# Sheet1.net
KiCad netlist of a schematic drawn in Altium Designer
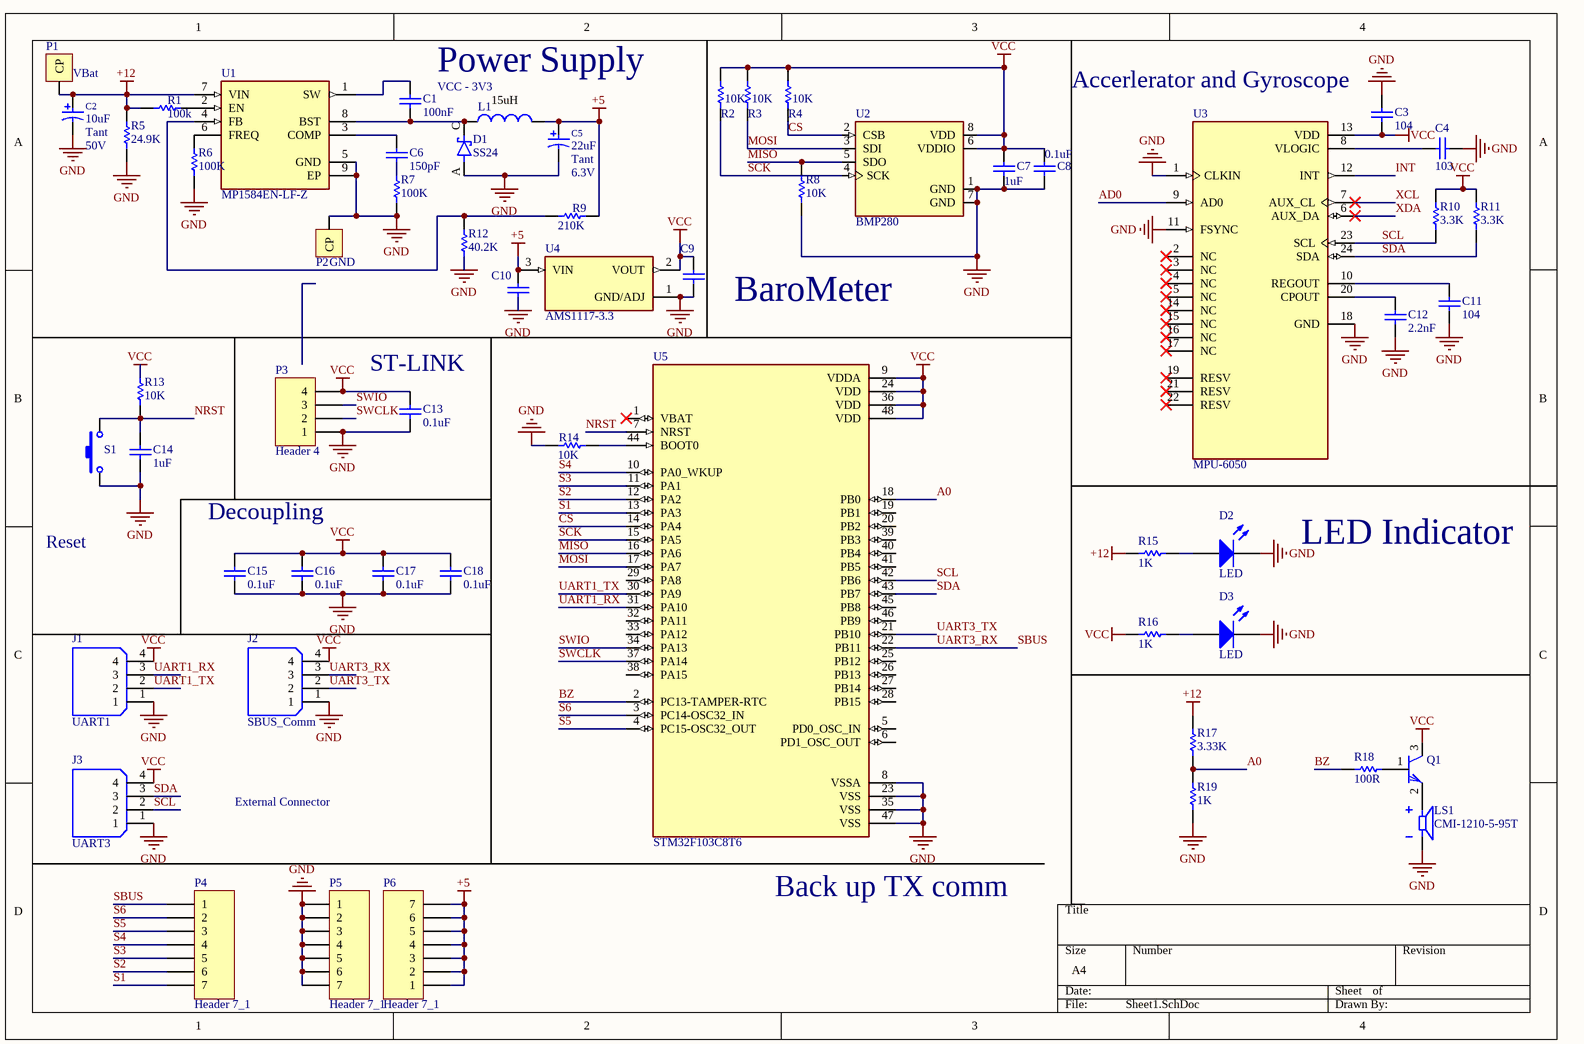
[diagram p0: Sheet1.SchDoc]

(export (version "E")
  (design (tool "Eeschema 10.0.6"))
  (components
    (comp (ref "C1")
      (value "100nF")
      (footprint "C-NP-0805")
      (description "Non-polarized Capacitor")
      (fields (field (name "Comment") "Cap Non-pol") (field (name "PUBLISHER") "Altium Limited"))
      (libsource (lib "Kiet") (part "Cap Non-pol"))
    )
    (comp (ref "C2")
      (value "10uF")
      (footprint "Cap_smd_4_3MM")
      (description "Polarized Capacitor")
      (fields
        (field (name "MANUFACTURER") "FARNELL")
        (field (name "CAPACITOR TYPE") "Tant")
        (field (name "VOLT") "50V")
        (field (name "PUBLISHER") "Hoang Nguyen")
      )
      (libsource (lib "Kiet") (part "Cap_Pol"))
    )
    (comp (ref "C3")
      (value "104")
      (footprint "C-NP-0805")
      (description "Non-polarized Capacitor")
      (fields (field (name "Comment") "Cap Non-pol") (field (name "PUBLISHER") "Altium Limited"))
      (libsource (lib "Kiet") (part "Cap Non-pol"))
    )
    (comp (ref "C4")
      (value "103")
      (footprint "C-NP-0805")
      (description "Non-polarized Capacitor")
      (fields (field (name "Comment") "Cap Non-pol") (field (name "PUBLISHER") "Altium Limited"))
      (libsource (lib "Kiet") (part "Cap Non-pol"))
    )
    (comp (ref "C5")
      (value "22uF")
      (footprint "Cap_smd_4_3MM")
      (description "Polarized Capacitor")
      (fields
        (field (name "MANUFACTURER") "FARNELL")
        (field (name "CAPACITOR TYPE") "Tant")
        (field (name "VOLT") "6.3V")
        (field (name "PUBLISHER") "Hoang Nguyen")
      )
      (libsource (lib "Kiet") (part "Cap_Pol"))
    )
    (comp (ref "C6")
      (value "150pF")
      (footprint "C-NP-0805")
      (description "Non-polarized Capacitor")
      (fields (field (name "Comment") "Cap Non-pol") (field (name "PUBLISHER") "Altium Limited"))
      (libsource (lib "Kiet") (part "Cap Non-pol"))
    )
    (comp (ref "C7")
      (value "1uF")
      (footprint "C-NP-0805")
      (description "Non-polarized Capacitor")
      (fields (field (name "Comment") "Cap Non-pol") (field (name "PUBLISHER") "Altium Limited"))
      (libsource (lib "Kiet") (part "Cap Non-pol"))
    )
    (comp (ref "C8")
      (value "0.1uF")
      (footprint "C-NP-0805")
      (description "Non-polarized Capacitor")
      (fields (field (name "Comment") "Cap Non-pol") (field (name "PUBLISHER") "Altium Limited"))
      (libsource (lib "Kiet") (part "Cap Non-pol"))
    )
    (comp (ref "C9")
      (value "Cap Non-pol")
      (footprint "C-NP-0805")
      (description "Non-polarized Capacitor")
      (fields (field (name "PUBLISHER") "Altium Limited"))
      (libsource (lib "Kiet") (part "Cap Non-pol"))
    )
    (comp (ref "C10")
      (value "Cap Non-pol")
      (footprint "C-NP-0805")
      (description "Non-polarized Capacitor")
      (fields (field (name "PUBLISHER") "Altium Limited"))
      (libsource (lib "Kiet") (part "Cap Non-pol"))
    )
    (comp (ref "C11")
      (value "104")
      (footprint "C-NP-0805")
      (description "Non-polarized Capacitor")
      (fields (field (name "Comment") "Cap Non-pol") (field (name "PUBLISHER") "Altium Limited"))
      (libsource (lib "Kiet") (part "Cap Non-pol"))
    )
    (comp (ref "C12")
      (value "2.2nF")
      (footprint "C-NP-0805")
      (description "Non-polarized Capacitor")
      (fields (field (name "Comment") "Cap Non-pol") (field (name "PUBLISHER") "Altium Limited"))
      (libsource (lib "Kiet") (part "Cap Non-pol"))
    )
    (comp (ref "C13")
      (value "0.1uF")
      (footprint "C-NP-0805")
      (description "Non-polarized Capacitor")
      (fields (field (name "Comment") "Cap Non-pol") (field (name "PUBLISHER") "Altium Limited"))
      (libsource (lib "Kiet") (part "Cap Non-pol"))
    )
    (comp (ref "C14")
      (value "1uF")
      (footprint "C-NP-0805")
      (description "Non-polarized Capacitor")
      (fields (field (name "Comment") "Cap Non-pol") (field (name "PUBLISHER") "Altium Limited"))
      (libsource (lib "Kiet") (part "Cap Non-pol"))
    )
    (comp (ref "C15")
      (value "0.1uF")
      (footprint "C-NP-0805")
      (description "Non-polarized Capacitor")
      (fields (field (name "Comment") "Cap Non-pol") (field (name "PUBLISHER") "Altium Limited"))
      (libsource (lib "Kiet") (part "Cap Non-pol"))
    )
    (comp (ref "C16")
      (value "0.1uF")
      (footprint "C-NP-0805")
      (description "Non-polarized Capacitor")
      (fields (field (name "Comment") "Cap Non-pol") (field (name "PUBLISHER") "Altium Limited"))
      (libsource (lib "Kiet") (part "Cap Non-pol"))
    )
    (comp (ref "C17")
      (value "0.1uF")
      (footprint "C-NP-0805")
      (description "Non-polarized Capacitor")
      (fields (field (name "Comment") "Cap Non-pol") (field (name "PUBLISHER") "Altium Limited"))
      (libsource (lib "Kiet") (part "Cap Non-pol"))
    )
    (comp (ref "C18")
      (value "0.1uF")
      (footprint "C-NP-0805")
      (description "Non-polarized Capacitor")
      (fields (field (name "Comment") "Cap Non-pol") (field (name "PUBLISHER") "Altium Limited"))
      (libsource (lib "Kiet") (part "Cap Non-pol"))
    )
    (comp (ref "D1")
      (value "SS24")
      (footprint "DIOM5336X265N")
      (description "Diode Schottky 40V 2A Surface Mount DO-214AA (SMB)")
      (fields (field (name "MF") "ON Semiconductor"))
      (libsource (lib "SS24") (part "SS24"))
    )
    (comp (ref "D2")
      (value "LED")
      (footprint "LED-0805 GREEN")
      (description "Typical LED")
      (fields (field (name "PUBLISHER") "Altium Limited"))
      (libsource (lib "Kiet") (part "LED"))
    )
    (comp (ref "D3")
      (value "LED")
      (footprint "LED-0805 GREEN")
      (description "Typical LED")
      (fields (field (name "PUBLISHER") "Altium Limited"))
      (libsource (lib "Kiet") (part "LED"))
    )
    (comp (ref "J1")
      (value "UART1")
      (footprint "AMPHENOL_10114830-11104LF")
      (fields
        (field (name "MF") "{'manufacturer': u'Amphenol ICC (FCI)'}")
        (field (name "MP") "10114830-11104LF")
      )
      (libsource (lib "1.25_SMD_4P_connector") (part "10114830-11104LF"))
    )
    (comp (ref "J2")
      (value "SBUS_Comm")
      (footprint "AMPHENOL_10114830-11104LF")
      (fields
        (field (name "MF") "{'manufacturer': u'Amphenol ICC (FCI)'}")
        (field (name "MP") "10114830-11104LF")
      )
      (libsource (lib "1.25_SMD_4P_connector") (part "10114830-11104LF"))
    )
    (comp (ref "J3")
      (value "UART3")
      (footprint "AMPHENOL_10114830-11104LF")
      (fields
        (field (name "MF") "{'manufacturer': u'Amphenol ICC (FCI)'}")
        (field (name "MP") "10114830-11104LF")
      )
      (libsource (lib "1.25_SMD_4P_connector") (part "10114830-11104LF"))
    )
    (comp (ref "L1")
      (value "15uH")
      (footprint "IMPE7-RS1")
      (description "Cuon Cam L")
      (fields (field (name "PUBLISHER") "Altium Limited"))
      (libsource (lib "Kiet") (part "Inductor_1"))
    )
    (comp (ref "LS1")
      (value "CMI-1210-5-95T")
      (footprint "XDCR_CMI-1210-5-95T")
      (description "12 mm, 5 Vdc, 98 dB, Through Hole, Magnetic Audio Indicator Buzzer")
      (fields (field (name "MF") "Same Sky"))
      (libsource (lib "Buzzer") (part "CMI-1210-5-95T"))
    )
    (comp (ref "P1")
      (value "VBat")
      (footprint "CP")
      (description "Connect Pad, 1-Pin")
      (fields (field (name "PUBLISHER") "Altium Limited"))
      (libsource (lib "Kiet") (part "Connect Pad"))
    )
    (comp (ref "P2")
      (value "GND")
      (footprint "CP")
      (description "Connect Pad, 1-Pin")
      (fields (field (name "PUBLISHER") "Altium Limited"))
      (libsource (lib "") (part "Connect Pad_1"))
    )
    (comp (ref "P3")
      (value "Header 4")
      (footprint "Header 4")
      (description "Header, 4-Pin")
      (fields (field (name "PUBLISHER") "Altium Limited"))
      (libsource (lib "Kiet") (part "Header 4"))
    )
    (comp (ref "P4")
      (value "Header 7_1")
      (footprint "HDR1X7")
      (description "Header, 7-Pin")
      (fields (field (name "PUBLISHER") "Altium Limited"))
      (libsource (lib "Kiet") (part "Header 7_1"))
    )
    (comp (ref "P5")
      (value "Header 7_1")
      (footprint "HDR1X7")
      (description "Header, 7-Pin")
      (fields (field (name "PUBLISHER") "Altium Limited"))
      (libsource (lib "Kiet") (part "Header 7_1"))
    )
    (comp (ref "P6")
      (value "Header 7_1")
      (footprint "HDR1X7")
      (description "Header, 7-Pin")
      (fields (field (name "PUBLISHER") "Altium Limited"))
      (libsource (lib "") (part "Header 7_1_1"))
    )
    (comp (ref "Q1")
      (value "C1815")
      (footprint "SOT23 [C1815]")
      (description "Q2SC1815")
      (fields (field (name "PUBLISHER") "Hoang Nguyen"))
      (libsource (lib "Kiet") (part "C1815"))
    )
    (comp (ref "R1")
      (value "100k")
      (footprint "R-0805")
      (description "Resistor")
      (fields (field (name "Comment") "RESISTOR") (field (name "PUBLISHER") "Altium Limited"))
      (libsource (lib "Kiet") (part "RESISTOR"))
    )
    (comp (ref "R2")
      (value "10K")
      (footprint "R-0805")
      (description "Resistor")
      (fields (field (name "Comment") "RESISTOR") (field (name "PUBLISHER") "Altium Limited"))
      (libsource (lib "Kiet") (part "RESISTOR"))
    )
    (comp (ref "R3")
      (value "10K")
      (footprint "R-0805")
      (description "Resistor")
      (fields (field (name "Comment") "RESISTOR") (field (name "PUBLISHER") "Altium Limited"))
      (libsource (lib "Kiet") (part "RESISTOR"))
    )
    (comp (ref "R4")
      (value "10K")
      (footprint "R-0805")
      (description "Resistor")
      (fields (field (name "Comment") "RESISTOR") (field (name "PUBLISHER") "Altium Limited"))
      (libsource (lib "Kiet") (part "RESISTOR"))
    )
    (comp (ref "R5")
      (value "24.9K")
      (footprint "R-0805")
      (description "Resistor")
      (fields (field (name "Comment") "RESISTOR") (field (name "PUBLISHER") "Altium Limited"))
      (libsource (lib "Kiet") (part "RESISTOR"))
    )
    (comp (ref "R6")
      (value "100K")
      (footprint "R-0805")
      (description "Resistor")
      (fields (field (name "Comment") "RESISTOR") (field (name "PUBLISHER") "Altium Limited"))
      (libsource (lib "Kiet") (part "RESISTOR"))
    )
    (comp (ref "R7")
      (value "100K")
      (footprint "R-0805")
      (description "Resistor")
      (fields (field (name "Comment") "RESISTOR") (field (name "PUBLISHER") "Altium Limited"))
      (libsource (lib "Kiet") (part "RESISTOR"))
    )
    (comp (ref "R8")
      (value "10K")
      (footprint "R-0805")
      (description "Resistor")
      (fields (field (name "Comment") "RESISTOR") (field (name "PUBLISHER") "Altium Limited"))
      (libsource (lib "Kiet") (part "RESISTOR"))
    )
    (comp (ref "R9")
      (value "210K")
      (footprint "R-0805")
      (description "Resistor")
      (fields (field (name "Comment") "RESISTOR") (field (name "PUBLISHER") "Altium Limited"))
      (libsource (lib "Kiet") (part "RESISTOR"))
    )
    (comp (ref "R10")
      (value "3.3K")
      (footprint "R-0805")
      (description "Resistor")
      (fields (field (name "Comment") "RESISTOR") (field (name "PUBLISHER") "Altium Limited"))
      (libsource (lib "Kiet") (part "RESISTOR"))
    )
    (comp (ref "R11")
      (value "3.3K")
      (footprint "R-0805")
      (description "Resistor")
      (fields (field (name "Comment") "RESISTOR") (field (name "PUBLISHER") "Altium Limited"))
      (libsource (lib "Kiet") (part "RESISTOR"))
    )
    (comp (ref "R12")
      (value "40.2K")
      (footprint "R-0805")
      (description "Resistor")
      (fields (field (name "Comment") "RESISTOR") (field (name "PUBLISHER") "Altium Limited"))
      (libsource (lib "Kiet") (part "RESISTOR"))
    )
    (comp (ref "R13")
      (value "10K")
      (footprint "R-0805")
      (description "Resistor")
      (fields (field (name "Comment") "RESISTOR") (field (name "PUBLISHER") "Altium Limited"))
      (libsource (lib "Kiet") (part "RESISTOR"))
    )
    (comp (ref "R14")
      (value "10K")
      (footprint "R-0805")
      (description "Resistor")
      (fields (field (name "Comment") "RESISTOR") (field (name "PUBLISHER") "Altium Limited"))
      (libsource (lib "Kiet") (part "RESISTOR"))
    )
    (comp (ref "R15")
      (value "1K")
      (footprint "R-0805")
      (description "Resistor")
      (fields (field (name "Comment") "RESISTOR") (field (name "PUBLISHER") "Altium Limited"))
      (libsource (lib "Kiet") (part "RESISTOR"))
    )
    (comp (ref "R16")
      (value "1K")
      (footprint "R-0805")
      (description "Resistor")
      (fields (field (name "Comment") "RESISTOR") (field (name "PUBLISHER") "Altium Limited"))
      (libsource (lib "Kiet") (part "RESISTOR"))
    )
    (comp (ref "R17")
      (value "3.33K")
      (footprint "R-0805")
      (description "Resistor")
      (fields (field (name "Comment") "RESISTOR") (field (name "PUBLISHER") "Altium Limited"))
      (libsource (lib "Kiet") (part "RESISTOR"))
    )
    (comp (ref "R18")
      (value "100R")
      (footprint "R-0805")
      (description "Resistor")
      (fields (field (name "Comment") "RESISTOR") (field (name "PUBLISHER") "Altium Limited"))
      (libsource (lib "Kiet") (part "RESISTOR"))
    )
    (comp (ref "R19")
      (value "1K")
      (footprint "R-0805")
      (description "Resistor")
      (fields (field (name "Comment") "RESISTOR") (field (name "PUBLISHER") "Altium Limited"))
      (libsource (lib "Kiet") (part "RESISTOR"))
    )
    (comp (ref "S1")
      (value "SW-SMD")
      (footprint "SW-SMD")
      (description "Switch")
      (fields (field (name "PUBLISHER") "Altium Limited"))
      (libsource (lib "Kiet") (part "SW-SMD"))
    )
    (comp (ref "U1")
      (value "MP1584EN-LF-Z")
      (footprint "SOIC127P600X170-9N")
      (fields (field (name "MF") "Monolithic Power Systems") (field (name "MP") "MP1584ENLFZ"))
      (libsource (lib "MP1584EN-LF-Z") (part "MP1584EN-LF-Z"))
    )
    (comp (ref "U2")
      (value "BMP280")
      (footprint "XDCR_BMP280")
      (description "BMP280 Absolute Barometric Pressure Sensor for Battery Powered Devices 2 x 2.5mm")
      (libsource (lib "BMP280") (part "BMP280"))
    )
    (comp (ref "U3")
      (value "MPU-6050")
      (footprint "QFN50P400X400X95-24N")
      (description "MPU-6050 series Accelerometer, Gyroscope, 3 Axis Sensor Evaluation Board")
      (fields (field (name "MF") "TDK InvenSense"))
      (libsource (lib "MPU-6050") (part "MPU-6050"))
    )
    (comp (ref "U4")
      (value "AMS1117-3.3")
      (footprint "SOT229P700X180-4N")
      (description "Sot223/Pkg 1-Amp 3.3-Volt Low Drop Out Voltage Regulatator")
      (fields (field (name "MF") "Advanced Monolithic Systems"))
      (libsource (lib "AMS1117-3.3") (part "AMS1117-3.3"))
    )
    (comp (ref "U5")
      (value "STM32F103C8T6")
      (footprint "QFP50P900X900X160-48N")
      (description "ARM® Cortex®-M3 STM32F1 Microcontroller IC 32-Bit 72MHz 64KB (64K x 8) FLASH 48-LQFP (7x7)")
      (fields (field (name "MF") "STMicroelectronics"))
      (libsource (lib "STM32F103C8T6") (part "STM32F103C8T6"))
    )
  )
  (nets
    (net (code "1") (name "+5") (class "Default")
      (node (ref "C10") (pin "1") (pinfunction "1_1") (pintype "passive"))
      (node (ref "C5") (pin "1") (pinfunction "1_1") (pintype "passive"))
      (node (ref "L1") (pin "2") (pinfunction "2_2") (pintype "passive"))
      (node (ref "P6") (pin "1") (pinfunction "1_1") (pintype "passive"))
      (node (ref "P6") (pin "2") (pinfunction "2_2") (pintype "passive"))
      (node (ref "P6") (pin "3") (pinfunction "3_3") (pintype "passive"))
      (node (ref "P6") (pin "4") (pinfunction "4_4") (pintype "passive"))
      (node (ref "P6") (pin "5") (pinfunction "5_5") (pintype "passive"))
      (node (ref "P6") (pin "6") (pinfunction "6_6") (pintype "passive"))
      (node (ref "P6") (pin "7") (pinfunction "7_7") (pintype "passive"))
      (node (ref "R9") (pin "1") (pinfunction "1_1") (pintype "passive"))
      (node (ref "U4") (pin "3") (pinfunction "VIN_3") (pintype "input"))
    )
    (net (code "2") (name "+12") (class "Default")
      (node (ref "C2") (pin "1") (pinfunction "1_1") (pintype "passive"))
      (node (ref "P1") (pin "1") (pinfunction "CP_1") (pintype "passive"))
      (node (ref "R1") (pin "1") (pinfunction "1_1") (pintype "passive"))
      (node (ref "R15") (pin "2") (pinfunction "2_2") (pintype "passive"))
      (node (ref "R17") (pin "1") (pinfunction "1_1") (pintype "passive"))
      (node (ref "R5") (pin "2") (pinfunction "2_2") (pintype "passive"))
      (node (ref "U1") (pin "7") (pinfunction "VIN_7") (pintype "input"))
    )
    (net (code "3") (name "/A0") (class "Default")
      (node (ref "R17") (pin "2") (pinfunction "2_2") (pintype "passive"))
      (node (ref "R19") (pin "1") (pinfunction "1_1") (pintype "passive"))
      (node (ref "U5") (pin "18") (pinfunction "PB0_18") (pintype "bidirectional"))
    )
    (net (code "4") (name "/AD0") (class "Default")
      (node (ref "U3") (pin "9") (pinfunction "AD0_9") (pintype "input"))
    )
    (net (code "5") (name "/BZ") (class "Default")
      (node (ref "R18") (pin "1") (pinfunction "1_1") (pintype "passive"))
      (node (ref "U5") (pin "2") (pinfunction "PC13-TAMPER-RTC_2") (pintype "bidirectional"))
    )
    (net (code "6") (name "/CS") (class "Default")
      (node (ref "R4") (pin "2") (pinfunction "2_2") (pintype "passive"))
      (node (ref "U2") (pin "2") (pinfunction "CSB_2") (pintype "input"))
      (node (ref "U5") (pin "14") (pinfunction "PA4_14") (pintype "bidirectional"))
    )
    (net (code "7") (name "/INT") (class "Default")
      (node (ref "U3") (pin "12") (pinfunction "INT_12") (pintype "output"))
    )
    (net (code "8") (name "/MISO") (class "Default")
      (node (ref "R8") (pin "1") (pinfunction "1_1") (pintype "passive"))
      (node (ref "U2") (pin "5") (pinfunction "SDO_5") (pintype "bidirectional"))
      (node (ref "U5") (pin "16") (pinfunction "PA6_16") (pintype "bidirectional"))
    )
    (net (code "9") (name "/MOSI") (class "Default")
      (node (ref "R3") (pin "2") (pinfunction "2_2") (pintype "passive"))
      (node (ref "U2") (pin "3") (pinfunction "SDI_3") (pintype "bidirectional"))
      (node (ref "U5") (pin "17") (pinfunction "PA7_17") (pintype "bidirectional"))
    )
    (net (code "10") (name "/NRST") (class "Default")
      (node (ref "C14") (pin "1") (pinfunction "1_1") (pintype "passive"))
      (node (ref "R13") (pin "2") (pinfunction "2_2") (pintype "passive"))
      (node (ref "S1") (pin "2") (pinfunction "2_2") (pintype "passive"))
      (node (ref "U5") (pin "7") (pinfunction "NRST_7") (pintype "input"))
    )
    (net (code "11") (name "/S1") (class "Default")
      (node (ref "P4") (pin "7") (pinfunction "7_7") (pintype "passive"))
      (node (ref "U5") (pin "13") (pinfunction "PA3_13") (pintype "bidirectional"))
    )
    (net (code "12") (name "/S2") (class "Default")
      (node (ref "P4") (pin "6") (pinfunction "6_6") (pintype "passive"))
      (node (ref "U5") (pin "12") (pinfunction "PA2_12") (pintype "bidirectional"))
    )
    (net (code "13") (name "/S3") (class "Default")
      (node (ref "P4") (pin "5") (pinfunction "5_5") (pintype "passive"))
      (node (ref "U5") (pin "11") (pinfunction "PA1_11") (pintype "bidirectional"))
    )
    (net (code "14") (name "/S4") (class "Default")
      (node (ref "P4") (pin "4") (pinfunction "4_4") (pintype "passive"))
      (node (ref "U5") (pin "10") (pinfunction "PA0_WKUP_10") (pintype "bidirectional"))
    )
    (net (code "15") (name "/S5") (class "Default")
      (node (ref "P4") (pin "3") (pinfunction "3_3") (pintype "passive"))
      (node (ref "U5") (pin "4") (pinfunction "PC15-OSC32_OUT_4") (pintype "bidirectional"))
    )
    (net (code "16") (name "/S6") (class "Default")
      (node (ref "P4") (pin "2") (pinfunction "2_2") (pintype "passive"))
      (node (ref "U5") (pin "3") (pinfunction "PC14-OSC32_IN_3") (pintype "bidirectional"))
    )
    (net (code "17") (name "/SBUS") (class "Default")
      (node (ref "J2") (pin "3") (pinfunction "3_3") (pintype "passive"))
      (node (ref "P4") (pin "1") (pinfunction "1_1") (pintype "passive"))
      (node (ref "U5") (pin "22") (pinfunction "PB11_22") (pintype "bidirectional"))
    )
    (net (code "18") (name "/SCK") (class "Default")
      (node (ref "R2") (pin "2") (pinfunction "2_2") (pintype "passive"))
      (node (ref "U2") (pin "4") (pinfunction "SCK_4") (pintype "input"))
      (node (ref "U5") (pin "15") (pinfunction "PA5_15") (pintype "bidirectional"))
    )
    (net (code "19") (name "/SCL") (class "Default")
      (node (ref "J3") (pin "2") (pinfunction "2_2") (pintype "passive"))
      (node (ref "R10") (pin "2") (pinfunction "2_2") (pintype "passive"))
      (node (ref "U3") (pin "23") (pinfunction "SCL_23") (pintype "input"))
      (node (ref "U5") (pin "42") (pinfunction "PB6_42") (pintype "bidirectional"))
    )
    (net (code "20") (name "/SDA") (class "Default")
      (node (ref "J3") (pin "3") (pinfunction "3_3") (pintype "passive"))
      (node (ref "R11") (pin "2") (pinfunction "2_2") (pintype "passive"))
      (node (ref "U3") (pin "24") (pinfunction "SDA_24") (pintype "bidirectional"))
      (node (ref "U5") (pin "43") (pinfunction "PB7_43") (pintype "bidirectional"))
    )
    (net (code "21") (name "/SWCLK") (class "Default")
      (node (ref "P3") (pin "2") (pinfunction "2_2") (pintype "passive"))
      (node (ref "U5") (pin "37") (pinfunction "PA14_37") (pintype "bidirectional"))
    )
    (net (code "22") (name "/SWIO") (class "Default")
      (node (ref "P3") (pin "3") (pinfunction "3_3") (pintype "passive"))
      (node (ref "U5") (pin "34") (pinfunction "PA13_34") (pintype "bidirectional"))
    )
    (net (code "23") (name "/UART1_RX") (class "Default")
      (node (ref "J1") (pin "3") (pinfunction "3_3") (pintype "passive"))
      (node (ref "U5") (pin "31") (pinfunction "PA10_31") (pintype "bidirectional"))
    )
    (net (code "24") (name "/UART1_TX") (class "Default")
      (node (ref "J1") (pin "2") (pinfunction "2_2") (pintype "passive"))
      (node (ref "U5") (pin "30") (pinfunction "PA9_30") (pintype "bidirectional"))
    )
    (net (code "25") (name "/UART3_TX") (class "Default")
      (node (ref "J2") (pin "2") (pinfunction "2_2") (pintype "passive"))
      (node (ref "U5") (pin "21") (pinfunction "PB10_21") (pintype "bidirectional"))
    )
    (net (code "26") (name "/XCL") (class "Default")
      (node (ref "U3") (pin "7") (pinfunction "AUX_CL_7") (pintype "output+no_connect"))
    )
    (net (code "27") (name "/XDA") (class "Default")
      (node (ref "U3") (pin "6") (pinfunction "AUX_DA_6") (pintype "bidirectional+no_connect"))
    )
    (net (code "28") (name "GND") (class "Default")
      (node (ref "C10") (pin "2") (pinfunction "2_2") (pintype "passive"))
      (node (ref "C11") (pin "1") (pinfunction "1_1") (pintype "passive"))
      (node (ref "C12") (pin "1") (pinfunction "1_1") (pintype "passive"))
      (node (ref "C13") (pin "2") (pinfunction "2_2") (pintype "passive"))
      (node (ref "C14") (pin "2") (pinfunction "2_2") (pintype "passive"))
      (node (ref "C15") (pin "2") (pinfunction "2_2") (pintype "passive"))
      (node (ref "C16") (pin "2") (pinfunction "2_2") (pintype "passive"))
      (node (ref "C17") (pin "2") (pinfunction "2_2") (pintype "passive"))
      (node (ref "C18") (pin "2") (pinfunction "2_2") (pintype "passive"))
      (node (ref "C2") (pin "2") (pinfunction "2_2") (pintype "passive"))
      (node (ref "C3") (pin "2") (pinfunction "2_2") (pintype "passive"))
      (node (ref "C4") (pin "2") (pinfunction "2_2") (pintype "passive"))
      (node (ref "C5") (pin "2") (pinfunction "2_2") (pintype "passive"))
      (node (ref "C7") (pin "2") (pinfunction "2_2") (pintype "passive"))
      (node (ref "C8") (pin "2") (pinfunction "2_2") (pintype "passive"))
      (node (ref "C9") (pin "1") (pinfunction "1_1") (pintype "passive"))
      (node (ref "D1") (pin "A") (pinfunction "A_A") (pintype "passive"))
      (node (ref "D2") (pin "2") (pinfunction "K_2") (pintype "passive"))
      (node (ref "D3") (pin "2") (pinfunction "K_2") (pintype "passive"))
      (node (ref "J1") (pin "1") (pinfunction "1_1") (pintype "passive"))
      (node (ref "J2") (pin "1") (pinfunction "1_1") (pintype "passive"))
      (node (ref "J3") (pin "1") (pinfunction "1_1") (pintype "passive"))
      (node (ref "LS1") (pin "N") (pinfunction "N_N") (pintype "passive"))
      (node (ref "P2") (pin "1") (pinfunction "CP_1") (pintype "passive"))
      (node (ref "P3") (pin "1") (pinfunction "1_1") (pintype "passive"))
      (node (ref "P5") (pin "1") (pinfunction "1_1") (pintype "passive"))
      (node (ref "P5") (pin "2") (pinfunction "2_2") (pintype "passive"))
      (node (ref "P5") (pin "3") (pinfunction "3_3") (pintype "passive"))
      (node (ref "P5") (pin "4") (pinfunction "4_4") (pintype "passive"))
      (node (ref "P5") (pin "5") (pinfunction "5_5") (pintype "passive"))
      (node (ref "P5") (pin "6") (pinfunction "6_6") (pintype "passive"))
      (node (ref "P5") (pin "7") (pinfunction "7_7") (pintype "passive"))
      (node (ref "R12") (pin "2") (pinfunction "2_2") (pintype "passive"))
      (node (ref "R14") (pin "2") (pinfunction "2_2") (pintype "passive"))
      (node (ref "R19") (pin "2") (pinfunction "2_2") (pintype "passive"))
      (node (ref "R5") (pin "1") (pinfunction "1_1") (pintype "passive"))
      (node (ref "R6") (pin "1") (pinfunction "1_1") (pintype "passive"))
      (node (ref "R7") (pin "1") (pinfunction "1_1") (pintype "passive"))
      (node (ref "R8") (pin "2") (pinfunction "2_2") (pintype "passive"))
      (node (ref "S1") (pin "1") (pinfunction "1_1") (pintype "passive"))
      (node (ref "U1") (pin "5") (pinfunction "GND_5") (pintype "power_in"))
      (node (ref "U1") (pin "9") (pinfunction "EP_9") (pintype "power_in"))
      (node (ref "U2") (pin "1") (pinfunction "GND_1") (pintype "power_in"))
      (node (ref "U2") (pin "7") (pinfunction "GND_7") (pintype "power_in"))
      (node (ref "U3") (pin "1") (pinfunction "CLKIN_1") (pintype "input"))
      (node (ref "U3") (pin "11") (pinfunction "FSYNC_11") (pintype "input"))
      (node (ref "U3") (pin "18") (pinfunction "GND_18") (pintype "power_in"))
      (node (ref "U4") (pin "1") (pinfunction "GND/ADJ_1") (pintype "power_in"))
      (node (ref "U5") (pin "23") (pinfunction "VSS_23") (pintype "power_in"))
      (node (ref "U5") (pin "35") (pinfunction "VSS_35") (pintype "power_in"))
      (node (ref "U5") (pin "47") (pinfunction "VSS_47") (pintype "power_in"))
      (node (ref "U5") (pin "8") (pinfunction "VSSA_8") (pintype "power_in"))
    )
    (net (code "29") (name "Net-(C6-Pad2)") (class "Default")
      (node (ref "C6") (pin "2") (pinfunction "2_2") (pintype "passive"))
      (node (ref "R7") (pin "2") (pinfunction "2_2") (pintype "passive"))
    )
    (net (code "30") (name "Net-(D1-K)") (class "Default")
      (node (ref "C1") (pin "2") (pinfunction "2_2") (pintype "passive"))
      (node (ref "D1") (pin "C") (pinfunction "K_C") (pintype "passive"))
      (node (ref "L1") (pin "1") (pinfunction "1_1") (pintype "passive"))
      (node (ref "U1") (pin "8") (pinfunction "BST_8") (pintype "passive"))
    )
    (net (code "31") (name "Net-(D2-A)") (class "Default")
      (node (ref "D2") (pin "1") (pinfunction "A_1") (pintype "passive"))
      (node (ref "R15") (pin "1") (pinfunction "1_1") (pintype "passive"))
    )
    (net (code "32") (name "Net-(D3-A)") (class "Default")
      (node (ref "D3") (pin "1") (pinfunction "A_1") (pintype "passive"))
      (node (ref "R16") (pin "1") (pinfunction "1_1") (pintype "passive"))
    )
    (net (code "33") (name "Net-(Q1-B)") (class "Default")
      (node (ref "Q1") (pin "1") (pinfunction "B_1") (pintype "passive"))
      (node (ref "R18") (pin "2") (pinfunction "2_2") (pintype "passive"))
    )
    (net (code "34") (name "Net-(Q1-E)") (class "Default")
      (node (ref "LS1") (pin "P") (pinfunction "P_P") (pintype "passive"))
      (node (ref "Q1") (pin "2") (pinfunction "E_2") (pintype "passive"))
    )
    (net (code "35") (name "Net-(U1-COMP)") (class "Default")
      (node (ref "C6") (pin "1") (pinfunction "1_1") (pintype "passive"))
      (node (ref "U1") (pin "3") (pinfunction "COMP_3") (pintype "passive"))
    )
    (net (code "36") (name "Net-(U1-EN)") (class "Default")
      (node (ref "R1") (pin "2") (pinfunction "2_2") (pintype "passive"))
      (node (ref "U1") (pin "2") (pinfunction "EN_2") (pintype "input"))
    )
    (net (code "37") (name "Net-(U1-FB)") (class "Default")
      (node (ref "R12") (pin "1") (pinfunction "1_1") (pintype "passive"))
      (node (ref "R9") (pin "2") (pinfunction "2_2") (pintype "passive"))
      (node (ref "U1") (pin "4") (pinfunction "FB_4") (pintype "input"))
    )
    (net (code "38") (name "Net-(U1-FREQ)") (class "Default")
      (node (ref "R6") (pin "2") (pinfunction "2_2") (pintype "passive"))
      (node (ref "U1") (pin "6") (pinfunction "FREQ_6") (pintype "passive"))
    )
    (net (code "39") (name "Net-(U1-SW)") (class "Default")
      (node (ref "C1") (pin "1") (pinfunction "1_1") (pintype "passive"))
      (node (ref "U1") (pin "1") (pinfunction "SW_1") (pintype "output"))
    )
    (net (code "40") (name "Net-(U3-CPOUT)") (class "Default")
      (node (ref "C12") (pin "2") (pinfunction "2_2") (pintype "passive"))
      (node (ref "U3") (pin "20") (pinfunction "CPOUT_20") (pintype "passive"))
    )
    (net (code "41") (name "Net-(U3-REGOUT)") (class "Default")
      (node (ref "C11") (pin "2") (pinfunction "2_2") (pintype "passive"))
      (node (ref "U3") (pin "10") (pinfunction "REGOUT_10") (pintype "passive"))
    )
    (net (code "42") (name "Net-(U3-VLOGIC)") (class "Default")
      (node (ref "C4") (pin "1") (pinfunction "1_1") (pintype "passive"))
      (node (ref "U3") (pin "8") (pinfunction "VLOGIC_8") (pintype "power_in"))
    )
    (net (code "43") (name "Net-(U5-BOOT0)") (class "Default")
      (node (ref "R14") (pin "1") (pinfunction "1_1") (pintype "passive"))
      (node (ref "U5") (pin "44") (pinfunction "BOOT0_44") (pintype "input"))
    )
    (net (code "44") (name "VCC") (class "Default")
      (node (ref "C13") (pin "1") (pinfunction "1_1") (pintype "passive"))
      (node (ref "C15") (pin "1") (pinfunction "1_1") (pintype "passive"))
      (node (ref "C16") (pin "1") (pinfunction "1_1") (pintype "passive"))
      (node (ref "C17") (pin "1") (pinfunction "1_1") (pintype "passive"))
      (node (ref "C18") (pin "1") (pinfunction "1_1") (pintype "passive"))
      (node (ref "C3") (pin "1") (pinfunction "1_1") (pintype "passive"))
      (node (ref "C7") (pin "1") (pinfunction "1_1") (pintype "passive"))
      (node (ref "C8") (pin "1") (pinfunction "1_1") (pintype "passive"))
      (node (ref "C9") (pin "2") (pinfunction "2_2") (pintype "passive"))
      (node (ref "J1") (pin "4") (pinfunction "4_4") (pintype "passive"))
      (node (ref "J2") (pin "4") (pinfunction "4_4") (pintype "passive"))
      (node (ref "J3") (pin "4") (pinfunction "4_4") (pintype "passive"))
      (node (ref "P3") (pin "4") (pinfunction "4_4") (pintype "passive"))
      (node (ref "Q1") (pin "3") (pinfunction "C_3") (pintype "passive"))
      (node (ref "R10") (pin "1") (pinfunction "1_1") (pintype "passive"))
      (node (ref "R11") (pin "1") (pinfunction "1_1") (pintype "passive"))
      (node (ref "R13") (pin "1") (pinfunction "1_1") (pintype "passive"))
      (node (ref "R16") (pin "2") (pinfunction "2_2") (pintype "passive"))
      (node (ref "R2") (pin "1") (pinfunction "1_1") (pintype "passive"))
      (node (ref "R3") (pin "1") (pinfunction "1_1") (pintype "passive"))
      (node (ref "R4") (pin "1") (pinfunction "1_1") (pintype "passive"))
      (node (ref "U2") (pin "6") (pinfunction "VDDIO_6") (pintype "power_in"))
      (node (ref "U2") (pin "8") (pinfunction "VDD_8") (pintype "power_in"))
      (node (ref "U3") (pin "13") (pinfunction "VDD_13") (pintype "power_in"))
      (node (ref "U4") (pin "2") (pinfunction "VOUT_2") (pintype "output"))
      (node (ref "U5") (pin "24") (pinfunction "VDD_24") (pintype "power_in"))
      (node (ref "U5") (pin "36") (pinfunction "VDD_36") (pintype "power_in"))
      (node (ref "U5") (pin "48") (pinfunction "VDD_48") (pintype "power_in"))
      (node (ref "U5") (pin "9") (pinfunction "VDDA_9") (pintype "power_in"))
    )
    (net (code "45") (name "unconnected-(U3-NC-Pad2)") (class "Default")
      (node (ref "U3") (pin "2") (pinfunction "NC_2") (pintype "passive+no_connect"))
    )
    (net (code "46") (name "unconnected-(U3-NC-Pad3)") (class "Default")
      (node (ref "U3") (pin "3") (pinfunction "NC_3") (pintype "passive+no_connect"))
    )
    (net (code "47") (name "unconnected-(U3-NC-Pad4)") (class "Default")
      (node (ref "U3") (pin "4") (pinfunction "NC_4") (pintype "passive+no_connect"))
    )
    (net (code "48") (name "unconnected-(U3-NC-Pad5)") (class "Default")
      (node (ref "U3") (pin "5") (pinfunction "NC_5") (pintype "passive+no_connect"))
    )
    (net (code "49") (name "unconnected-(U3-NC-Pad14)") (class "Default")
      (node (ref "U3") (pin "14") (pinfunction "NC_14") (pintype "passive+no_connect"))
    )
    (net (code "50") (name "unconnected-(U3-NC-Pad15)") (class "Default")
      (node (ref "U3") (pin "15") (pinfunction "NC_15") (pintype "passive+no_connect"))
    )
    (net (code "51") (name "unconnected-(U3-NC-Pad16)") (class "Default")
      (node (ref "U3") (pin "16") (pinfunction "NC_16") (pintype "passive+no_connect"))
    )
    (net (code "52") (name "unconnected-(U3-NC-Pad17)") (class "Default")
      (node (ref "U3") (pin "17") (pinfunction "NC_17") (pintype "passive+no_connect"))
    )
    (net (code "53") (name "unconnected-(U3-RESV-Pad19)") (class "Default")
      (node (ref "U3") (pin "19") (pinfunction "RESV_19") (pintype "passive+no_connect"))
    )
    (net (code "54") (name "unconnected-(U3-RESV-Pad21)") (class "Default")
      (node (ref "U3") (pin "21") (pinfunction "RESV_21") (pintype "passive+no_connect"))
    )
    (net (code "55") (name "unconnected-(U3-RESV-Pad22)") (class "Default")
      (node (ref "U3") (pin "22") (pinfunction "RESV_22") (pintype "passive+no_connect"))
    )
    (net (code "56") (name "unconnected-(U5-PA8-Pad29)") (class "Default")
      (node (ref "U5") (pin "29") (pinfunction "PA8_29") (pintype "bidirectional"))
    )
    (net (code "57") (name "unconnected-(U5-PA11-Pad32)") (class "Default")
      (node (ref "U5") (pin "32") (pinfunction "PA11_32") (pintype "bidirectional"))
    )
    (net (code "58") (name "unconnected-(U5-PA12-Pad33)") (class "Default")
      (node (ref "U5") (pin "33") (pinfunction "PA12_33") (pintype "bidirectional"))
    )
    (net (code "59") (name "unconnected-(U5-PA15-Pad38)") (class "Default")
      (node (ref "U5") (pin "38") (pinfunction "PA15_38") (pintype "bidirectional"))
    )
    (net (code "60") (name "unconnected-(U5-PB1-Pad19)") (class "Default")
      (node (ref "U5") (pin "19") (pinfunction "PB1_19") (pintype "bidirectional"))
    )
    (net (code "61") (name "unconnected-(U5-PB2-Pad20)") (class "Default")
      (node (ref "U5") (pin "20") (pinfunction "PB2_20") (pintype "bidirectional"))
    )
    (net (code "62") (name "unconnected-(U5-PB3-Pad39)") (class "Default")
      (node (ref "U5") (pin "39") (pinfunction "PB3_39") (pintype "bidirectional"))
    )
    (net (code "63") (name "unconnected-(U5-PB4-Pad40)") (class "Default")
      (node (ref "U5") (pin "40") (pinfunction "PB4_40") (pintype "bidirectional"))
    )
    (net (code "64") (name "unconnected-(U5-PB5-Pad41)") (class "Default")
      (node (ref "U5") (pin "41") (pinfunction "PB5_41") (pintype "bidirectional"))
    )
    (net (code "65") (name "unconnected-(U5-PB8-Pad45)") (class "Default")
      (node (ref "U5") (pin "45") (pinfunction "PB8_45") (pintype "bidirectional"))
    )
    (net (code "66") (name "unconnected-(U5-PB9-Pad46)") (class "Default")
      (node (ref "U5") (pin "46") (pinfunction "PB9_46") (pintype "bidirectional"))
    )
    (net (code "67") (name "unconnected-(U5-PB12-Pad25)") (class "Default")
      (node (ref "U5") (pin "25") (pinfunction "PB12_25") (pintype "bidirectional"))
    )
    (net (code "68") (name "unconnected-(U5-PB13-Pad26)") (class "Default")
      (node (ref "U5") (pin "26") (pinfunction "PB13_26") (pintype "bidirectional"))
    )
    (net (code "69") (name "unconnected-(U5-PB14-Pad27)") (class "Default")
      (node (ref "U5") (pin "27") (pinfunction "PB14_27") (pintype "bidirectional"))
    )
    (net (code "70") (name "unconnected-(U5-PB15-Pad28)") (class "Default")
      (node (ref "U5") (pin "28") (pinfunction "PB15_28") (pintype "bidirectional"))
    )
    (net (code "71") (name "unconnected-(U5-PD0_OSC_IN-Pad5)") (class "Default")
      (node (ref "U5") (pin "5") (pinfunction "PD0_OSC_IN_5") (pintype "bidirectional"))
    )
    (net (code "72") (name "unconnected-(U5-PD1_OSC_OUT-Pad6)") (class "Default")
      (node (ref "U5") (pin "6") (pinfunction "PD1_OSC_OUT_6") (pintype "bidirectional"))
    )
    (net (code "73") (name "unconnected-(U5-VBAT-Pad1)") (class "Default")
      (node (ref "U5") (pin "1") (pinfunction "VBAT_1") (pintype "bidirectional+no_connect"))
    )
  )
)
